# dc-dc_stepup_converter.net
KiCad netlist of a schematic drawn in Altium Designer
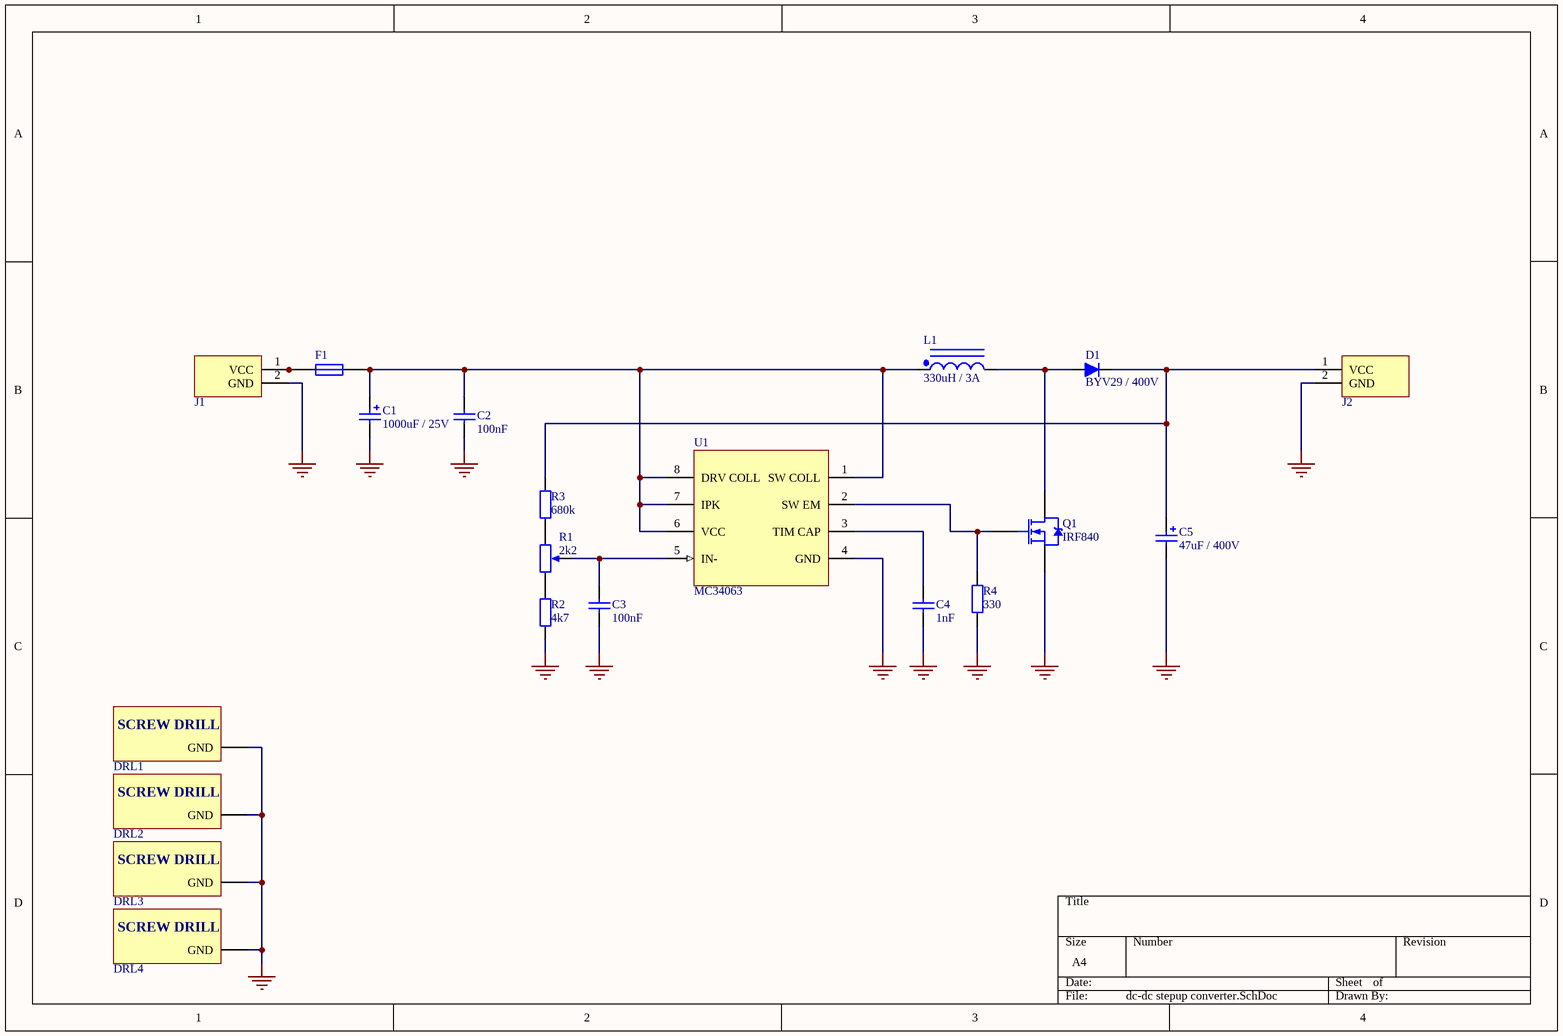
[diagram p0: dc-dc stepup converter.SchDoc]

(export (version "E")
  (design (tool "Eeschema 10.0.6"))
  (components
    (comp (ref "C1")
      (value "1000uF / 25V")
      (footprint "CAPPR5-10x20_MANUAL")
      (description "Polarized Capacitor")
      (libsource (lib "main_lib") (part "Cap Pol"))
    )
    (comp (ref "C2")
      (value "100nF")
      (footprint "CAPR5.08-7.8X3.2_MANUAL")
      (description "Capacitor")
      (libsource (lib "main_lib") (part "Cap"))
    )
    (comp (ref "C3")
      (value "100nF")
      (footprint "CAPR5.08-7.8X3.2_MANUAL")
      (description "Capacitor")
      (libsource (lib "main_lib") (part "Cap"))
    )
    (comp (ref "C4")
      (value "1nF")
      (footprint "CAPR5.08-7.8X3.2_MANUAL")
      (description "Capacitor")
      (libsource (lib "main_lib") (part "Cap"))
    )
    (comp (ref "C5")
      (value "47uF / 400V")
      (footprint "CAPPR7.5-16.5x30_MANUAL")
      (description "Polarized Capacitor")
      (libsource (lib "main_lib_sch") (part "Cap Pol"))
    )
    (comp (ref "D1")
      (value "BYV29 / 400V")
      (footprint "TO220/2")
      (description "Rectifier diodes ultrafast")
      (libsource (lib "main_lib") (part "BYV29"))
    )
    (comp (ref "DRL1")
      (value "SCREW DRILL")
      (footprint "3mm screw drill I")
      (description "Screw Drill")
      (libsource (lib "main_lib") (part "SCREW DRILL"))
    )
    (comp (ref "DRL2")
      (value "SCREW DRILL")
      (footprint "3mm screw drill I")
      (description "Screw Drill")
      (libsource (lib "main_lib") (part "SCREW DRILL"))
    )
    (comp (ref "DRL3")
      (value "SCREW DRILL")
      (footprint "3mm screw drill I")
      (description "Screw Drill")
      (libsource (lib "main_lib") (part "SCREW DRILL"))
    )
    (comp (ref "DRL4")
      (value "SCREW DRILL")
      (footprint "3mm screw drill I")
      (description "Screw Drill")
      (libsource (lib "main_lib") (part "SCREW DRILL"))
    )
    (comp (ref "F1")
      (value "~")
      (footprint "Bezp 5x20 uniw")
      (description "Fuse")
      (libsource (lib "main_lib_sch") (part "Fuse"))
    )
    (comp (ref "J1")
      (value "ARK2_power")
      (footprint "ARK2/3.5mm pitch")
      (libsource (lib "connectors") (part "ARK2_power"))
    )
    (comp (ref "J2")
      (value "ARK2_power")
      (footprint "ARK2/3.5mm pitch")
      (libsource (lib "") (part "ARK2_power_1"))
    )
    (comp (ref "L1")
      (value "330uH / 3A")
      (footprint "IND_15.4_PIONOWO")
      (description "Magnetic-Core Inductor with Winding Polarity Marking")
      (libsource (lib "main_lib_sch") (part "InducCore"))
    )
    (comp (ref "Q1")
      (value "IRF840")
      (footprint "TO220")
      (description "N-Channel Power MOSFET")
      (libsource (lib "main_lib") (part "IRF840"))
    )
    (comp (ref "R1")
      (value "2k2")
      (footprint "RPot_wieloob_19mm_lezacy")
      (description "Potentiometer")
      (libsource (lib "main_lib_sch") (part "RPot"))
    )
    (comp (ref "R2")
      (value "4k7")
      (footprint "RES10.55-7X2.8_MANUAL")
      (description "Resistor")
      (libsource (lib "main_lib") (part "Res"))
    )
    (comp (ref "R3")
      (value "680k")
      (footprint "RES10.55-7X2.8_MANUAL")
      (description "Resistor")
      (libsource (lib "main_lib") (part "Res"))
    )
    (comp (ref "R4")
      (value "330")
      (footprint "RES10.55-7X2.8_MANUAL")
      (description "Resistor")
      (libsource (lib "main_lib") (part "Res"))
    )
    (comp (ref "U1")
      (value "MC34063")
      (footprint "DIP8_MANUAL")
      (description "DC-to-DC Converter Control Circuit")
      (libsource (lib "main_lib") (part "MC34063"))
    )
  )
  (nets
    (net (code "1") (name "GND") (class "Default")
      (node (ref "C1") (pin "2") (pinfunction "2_2") (pintype "passive"))
      (node (ref "C2") (pin "1") (pinfunction "1_1") (pintype "passive"))
      (node (ref "C3") (pin "1") (pinfunction "1_1") (pintype "passive"))
      (node (ref "C4") (pin "1") (pinfunction "1_1") (pintype "passive"))
      (node (ref "C5") (pin "2") (pinfunction "2_2") (pintype "passive"))
      (node (ref "DRL1") (pin "0") (pinfunction "GND_0") (pintype "passive"))
      (node (ref "DRL2") (pin "0") (pinfunction "GND_0") (pintype "passive"))
      (node (ref "DRL3") (pin "0") (pinfunction "GND_0") (pintype "passive"))
      (node (ref "DRL4") (pin "0") (pinfunction "GND_0") (pintype "passive"))
      (node (ref "J1") (pin "2") (pinfunction "GND_2") (pintype "passive"))
      (node (ref "J2") (pin "2") (pinfunction "GND_2") (pintype "passive"))
      (node (ref "Q1") (pin "3") (pinfunction "S_3") (pintype "passive"))
      (node (ref "R2") (pin "1") (pinfunction "1_1") (pintype "passive"))
      (node (ref "R4") (pin "1") (pinfunction "1_1") (pintype "passive"))
      (node (ref "U1") (pin "4") (pinfunction "GND_4") (pintype "power_in"))
    )
    (net (code "2") (name "Net-(D1-A)") (class "Default")
      (node (ref "D1") (pin "1") (pinfunction "A_1") (pintype "passive"))
      (node (ref "L1") (pin "2") (pinfunction "2_2") (pintype "passive"))
      (node (ref "Q1") (pin "2") (pinfunction "D_2") (pintype "passive"))
    )
    (net (code "3") (name "Net-(D1-K)") (class "Default")
      (node (ref "C5") (pin "1") (pinfunction "1_1") (pintype "passive"))
      (node (ref "D1") (pin "2") (pinfunction "K_2") (pintype "passive"))
      (node (ref "J2") (pin "1") (pinfunction "VCC_1") (pintype "passive"))
      (node (ref "R3") (pin "2") (pinfunction "2_2") (pintype "passive"))
    )
    (net (code "4") (name "Net-(J1-VCC)") (class "Default")
      (node (ref "F1") (pin "1") (pinfunction "1_1") (pintype "passive"))
      (node (ref "F1") (pin "3") (pinfunction "3_3") (pintype "passive"))
      (node (ref "F1") (pin "5") (pinfunction "5_5") (pintype "passive"))
      (node (ref "F1") (pin "7") (pinfunction "7_7") (pintype "passive"))
      (node (ref "J1") (pin "1") (pinfunction "VCC_1") (pintype "passive"))
    )
    (net (code "5") (name "Net-(Q1-G)") (class "Default")
      (node (ref "Q1") (pin "1") (pinfunction "G_1") (pintype "passive"))
      (node (ref "R4") (pin "2") (pinfunction "2_2") (pintype "passive"))
      (node (ref "U1") (pin "2") (pinfunction "SW_EM_2") (pintype "passive"))
    )
    (net (code "6") (name "Net-(R1-BOT)") (class "Default")
      (node (ref "R1") (pin "2") (pinfunction "BOT_2") (pintype "passive"))
      (node (ref "R3") (pin "1") (pinfunction "1_1") (pintype "passive"))
    )
    (net (code "7") (name "Net-(R1-TAP)") (class "Default")
      (node (ref "C3") (pin "2") (pinfunction "2_2") (pintype "passive"))
      (node (ref "R1") (pin "3") (pinfunction "TAP_3") (pintype "passive"))
      (node (ref "U1") (pin "5") (pinfunction "IN-_5") (pintype "input"))
    )
    (net (code "8") (name "Net-(R1-TOP)") (class "Default")
      (node (ref "R1") (pin "1") (pinfunction "TOP_1") (pintype "passive"))
      (node (ref "R2") (pin "2") (pinfunction "2_2") (pintype "passive"))
    )
    (net (code "9") (name "Net-(U1-DRV_COLL)") (class "Default")
      (node (ref "C1") (pin "1") (pinfunction "1_1") (pintype "passive"))
      (node (ref "C2") (pin "2") (pinfunction "2_2") (pintype "passive"))
      (node (ref "F1") (pin "2") (pinfunction "2_2") (pintype "passive"))
      (node (ref "F1") (pin "4") (pinfunction "4_4") (pintype "passive"))
      (node (ref "F1") (pin "6") (pinfunction "6_6") (pintype "passive"))
      (node (ref "F1") (pin "8") (pinfunction "8_8") (pintype "passive"))
      (node (ref "L1") (pin "1") (pinfunction "1_1") (pintype "passive"))
      (node (ref "U1") (pin "1") (pinfunction "SW_COLL_1") (pintype "passive"))
      (node (ref "U1") (pin "6") (pinfunction "VCC_6") (pintype "power_in"))
      (node (ref "U1") (pin "7") (pinfunction "IPK_7") (pintype "passive"))
      (node (ref "U1") (pin "8") (pinfunction "DRV_COLL_8") (pintype "open_collector"))
    )
    (net (code "10") (name "Net-(U1-TIM_CAP)") (class "Default")
      (node (ref "C4") (pin "2") (pinfunction "2_2") (pintype "passive"))
      (node (ref "U1") (pin "3") (pinfunction "TIM_CAP_3") (pintype "passive"))
    )
  )
)
